# TinyDuino-noboard.net
KiCad netlist of a schematic drawn in EAGLE
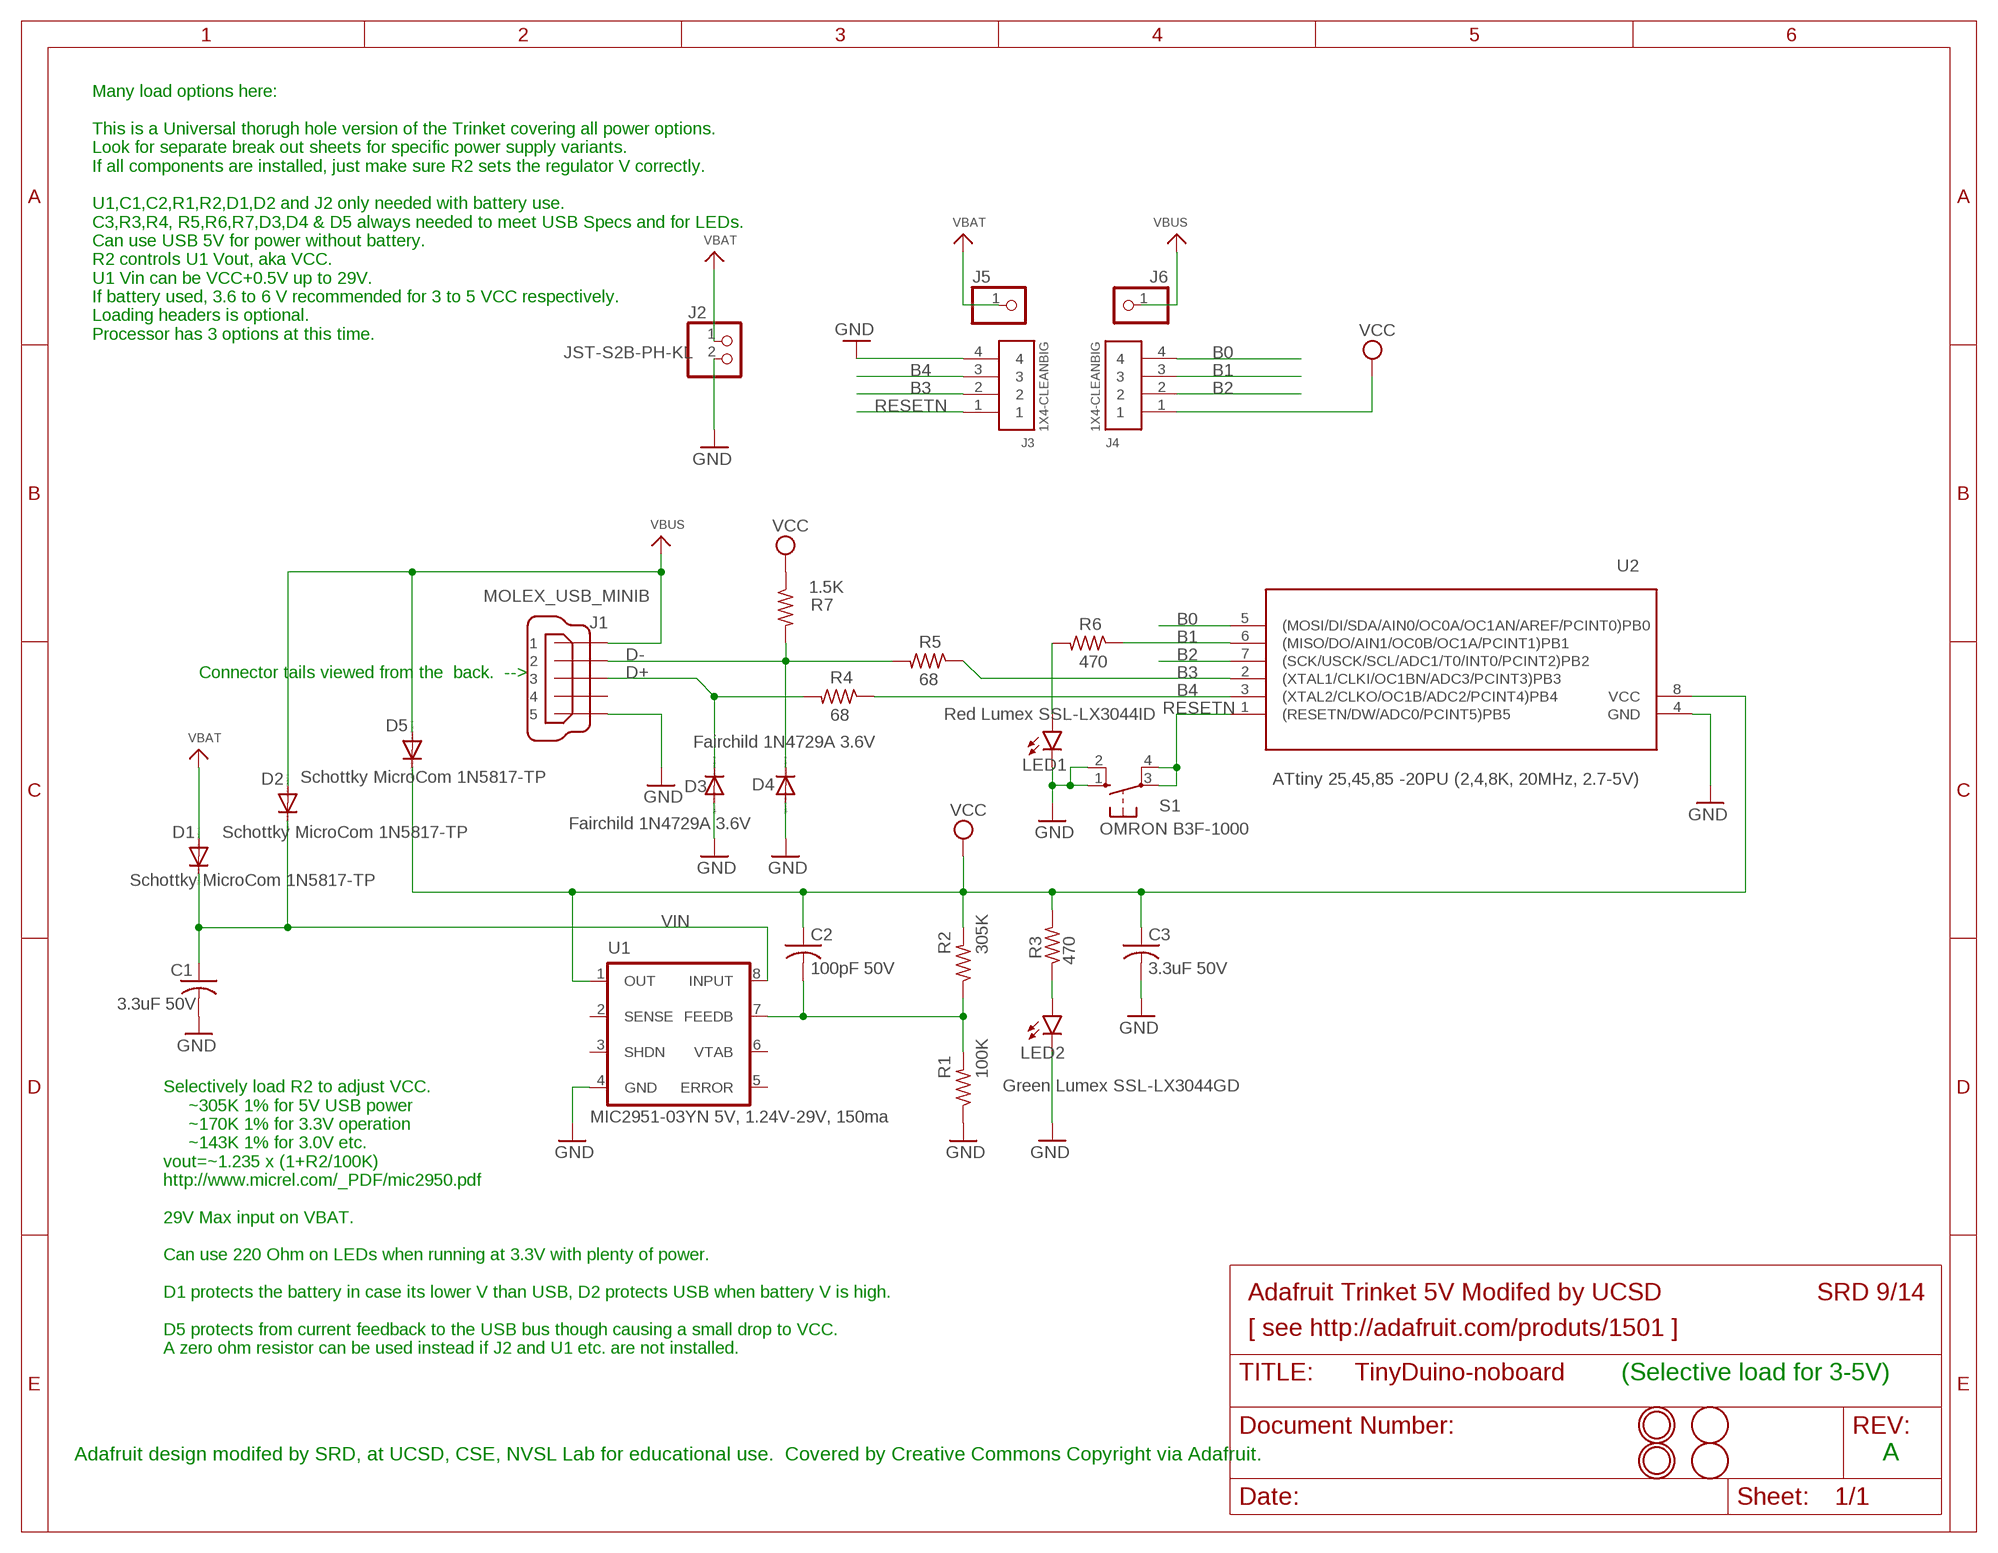
[diagram p0: schematic, sheet 1]

(export (version "E")
  (design (tool "Eeschema 10.0.6"))
  (components
    (comp (ref "C1")
      (value "3.3uF 50V")
      (footprint "eagle-import:C050-025X075")
      (fields (field (name "MFR") "TDK") (field (name "PARTNO") "FK20X7R1H335K"))
      (libsource (lib "eagle-import") (part "C-US050-025X075"))
    )
    (comp (ref "C2")
      (value "100pF 50V")
      (footprint "eagle-import:C050-025X075")
      (fields (field (name "MFR") "TDK") (field (name "PARTNO") "FK28C0G1H101J"))
      (libsource (lib "eagle-import") (part "C-US050-025X075"))
    )
    (comp (ref "C3")
      (value "3.3uF 50V")
      (footprint "eagle-import:C050-025X075")
      (fields (field (name "MFR") "TDK") (field (name "PARTNO") "FK20X7R1H335K"))
      (libsource (lib "eagle-import") (part "C-US050-025X075"))
    )
    (comp (ref "D1")
      (value "Schottky MicroCom 1N5817-TP")
      (footprint "eagle-import:DO41-7.6")
      (fields (field (name "MFR") "Micro Com.") (field (name "PARTNO") "1N5817-TP"))
      (libsource (lib "eagle-import") (part "DIODE-DO41-7.6"))
    )
    (comp (ref "D2")
      (value "Schottky MicroCom 1N5817-TP")
      (footprint "eagle-import:DO41-7.6")
      (fields (field (name "MFR") "Micro Com.") (field (name "PARTNO") "1N5817-TP"))
      (libsource (lib "eagle-import") (part "DIODE-DO41-7.6"))
    )
    (comp (ref "D3")
      (value "Fairchild 1N4729A 3.6V")
      (footprint "eagle-import:DO41-7.6")
      (fields (field (name "MFR") "Fairchild") (field (name "PARTNO") "1N4729A"))
      (libsource (lib "eagle-import") (part "DIODE-DO41-7.6"))
    )
    (comp (ref "D4")
      (value "Fairchild 1N4729A 3.6V")
      (footprint "eagle-import:DO41-7.6")
      (fields (field (name "MFR") "Fairchild") (field (name "PARTNO") "1N4729A"))
      (libsource (lib "eagle-import") (part "DIODE-DO41-7.6"))
    )
    (comp (ref "D5")
      (value "Schottky MicroCom 1N5817-TP")
      (footprint "eagle-import:DO41-7.6")
      (fields (field (name "MFR") "Micro Com.") (field (name "PARTNO") "1N5817-TP"))
      (libsource (lib "eagle-import") (part "DIODE-DO41-7.6"))
    )
    (comp (ref "J1")
      (value "MOLEX_USB_MINIB")
      (footprint "eagle-import:32005-601-ROUND")
      (fields (field (name "MFR") "Molex") (field (name "PARTNO") "0548190519"))
      (libsource (lib "eagle-import") (part "MOLEX_USB_MINIB"))
    )
    (comp (ref "J2")
      (value "JST-S2B-PH-KL")
      (footprint "eagle-import:JST_S2B_PH_KL")
      (fields (field (name "MFR") "JST") (field (name "PARTNO") "JST_S2B_PH_KL"))
      (libsource (lib "eagle-import") (part "CON_JST_PH_2PINJST_S2B_PH_KL"))
    )
    (comp (ref "J3")
      (value "1X4-CLEANBIG")
      (footprint "eagle-import:1X04-CLEANBIG")
      (libsource (lib "eagle-import") (part "1X4-CLEANBIG"))
    )
    (comp (ref "J4")
      (value "1X4-CLEANBIG")
      (footprint "eagle-import:1X04-CLEANBIG")
      (libsource (lib "eagle-import") (part "1X4-CLEANBIG"))
    )
    (comp (ref "J5")
      (value "PINHD-1X1CB")
      (footprint "eagle-import:1X01-CLEANBIG")
      (libsource (lib "eagle-import") (part "PINHD-1X1CB"))
    )
    (comp (ref "J6")
      (value "PINHD-1X1CB")
      (footprint "eagle-import:1X01-CLEANBIG")
      (libsource (lib "eagle-import") (part "PINHD-1X1CB"))
    )
    (comp (ref "LED1")
      (value "Red Lumex SSL-LX3044ID")
      (footprint "eagle-import:LED3MM")
      (fields (field (name "MFR") "Lumex") (field (name "PARTNO") "SSL-LX3044ID"))
      (libsource (lib "eagle-import") (part "LED3MM"))
    )
    (comp (ref "LED2")
      (value "Green Lumex SSL-LX3044GD")
      (footprint "eagle-import:LED3MM")
      (fields (field (name "MFR") "Lumex") (field (name "PARTNO") "SSL-LX3044GD"))
      (libsource (lib "eagle-import") (part "LED3MM"))
    )
    (comp (ref "R1")
      (value "100K")
      (footprint "eagle-import:0204_7")
      (fields (field (name "MFR") "Yageo") (field (name "PARTNO") "MFR-25FBF52-100K"))
      (libsource (lib "eagle-import") (part "R-US_0204/7"))
    )
    (comp (ref "R2")
      (value "305K")
      (footprint "eagle-import:0204_7")
      (fields (field (name "MFR") "Yageo") (field (name "PARTNO") "MFR-25FBF52-301K"))
      (libsource (lib "eagle-import") (part "R-US_0204/7"))
    )
    (comp (ref "R3")
      (value "470")
      (footprint "eagle-import:0204_7")
      (fields (field (name "MFR") "Yageo") (field (name "PARTNO") "CFR-12JB-52-470R"))
      (libsource (lib "eagle-import") (part "R-US_0204/7"))
    )
    (comp (ref "R4")
      (value "68")
      (footprint "eagle-import:0204_7")
      (fields (field (name "MFR") "Yageo") (field (name "PARTNO") "CFR-12JB-52-68R"))
      (libsource (lib "eagle-import") (part "R-US_0204/7"))
    )
    (comp (ref "R5")
      (value "68")
      (footprint "eagle-import:0204_7")
      (fields (field (name "MFR") "Yageo") (field (name "PARTNO") "CFR-12JB-52-68R"))
      (libsource (lib "eagle-import") (part "R-US_0204/7"))
    )
    (comp (ref "R6")
      (value "470")
      (footprint "eagle-import:0204_7")
      (fields (field (name "MFR") "Yageo") (field (name "PARTNO") "CFR-12JB-52-470R"))
      (libsource (lib "eagle-import") (part "R-US_0204/7"))
    )
    (comp (ref "R7")
      (value "1.5K")
      (footprint "eagle-import:0204_7")
      (fields (field (name "MFR") "Yageo") (field (name "PARTNO") "CFR-12JB-52-1K5"))
      (libsource (lib "eagle-import") (part "R-US_0204/7"))
    )
    (comp (ref "S1")
      (value "OMRON B3F-1000")
      (footprint "eagle-import:B3F-10XX")
      (fields (field (name "MPN") "B3F-1000") (field (name "MFR") "Omron"))
      (libsource (lib "eagle-import") (part "10-XX"))
    )
    (comp (ref "U1")
      (value "MIC2951-03YN 5V, 1.24V-29V, 150ma")
      (footprint "eagle-import:DIL08")
      (fields (field (name "MFR") "Micrel") (field (name "PARTNO") "MIC2951-03YN"))
      (libsource (lib "eagle-import") (part "MIC2951-03YNCN"))
    )
    (comp (ref "U2")
      (value "ATtiny 25,45,85 -20PU (2,4,8K, 20MHz, 2.7-5V)")
      (footprint "eagle-import:DIL08")
      (fields (field (name "MFR") "Atmel") (field (name "PARTNO") "ATTINY85-20PU-ND"))
      (libsource (lib "eagle-import") (part "ATTINY85P-20"))
    )
    (comp (ref "Z1")
      (value "MOUNTINGHOLE2.0")
      (footprint "eagle-import:MOUNTINGHOLE_2.0_PLATED")
      (libsource (lib "eagle-import") (part "MOUNTINGHOLE2.0"))
    )
    (comp (ref "Z2")
      (value "MOUNTINGHOLE2.0")
      (footprint "eagle-import:MOUNTINGHOLE_2.0_PLATED")
      (libsource (lib "eagle-import") (part "MOUNTINGHOLE2.0"))
    )
    (comp (ref "Z3")
      (value "FIDUCIAL")
      (footprint "eagle-import:FIDUCIAL_1MM")
      (libsource (lib "eagle-import") (part "FIDUCIAL"))
    )
    (comp (ref "Z4")
      (value "FIDUCIAL")
      (footprint "eagle-import:FIDUCIAL_1MM")
      (libsource (lib "eagle-import") (part "FIDUCIAL"))
    )
  )
  (nets
    (net (code "1") (name "/B0") (class "Default")
      (node (ref "J4") (pin "4") (pinfunction "4_4") (pintype "bidirectional"))
      (node (ref "U2") (pin "5") (pinfunction "(MOSI/DI/SDA/AIN0/OC0A/OC1AN/AREF/PCINT0)PB0_5") (pintype "bidirectional"))
    )
    (net (code "2") (name "/B1") (class "Default")
      (node (ref "J4") (pin "3") (pinfunction "3_3") (pintype "bidirectional"))
      (node (ref "R6") (pin "1") (pinfunction "1_1") (pintype "passive"))
      (node (ref "U2") (pin "6") (pinfunction "(MISO/DO/AIN1/OC0B/OC1A/PCINT1)PB1_6") (pintype "bidirectional"))
    )
    (net (code "3") (name "/B2") (class "Default")
      (node (ref "J4") (pin "2") (pinfunction "2_2") (pintype "bidirectional"))
      (node (ref "U2") (pin "7") (pinfunction "(SCK/USCK/SCL/ADC1/T0/INT0/PCINT2)PB2_7") (pintype "bidirectional"))
    )
    (net (code "4") (name "/B3") (class "Default")
      (node (ref "J3") (pin "2") (pinfunction "2_2") (pintype "bidirectional"))
      (node (ref "R5") (pin "1") (pinfunction "1_1") (pintype "passive"))
      (node (ref "U2") (pin "2") (pinfunction "(XTAL1/CLKI/OC1BN/ADC3/PCINT3)PB3_2") (pintype "bidirectional"))
    )
    (net (code "5") (name "/B4") (class "Default")
      (node (ref "J3") (pin "3") (pinfunction "3_3") (pintype "bidirectional"))
      (node (ref "R4") (pin "1") (pinfunction "1_1") (pintype "passive"))
      (node (ref "U2") (pin "3") (pinfunction "(XTAL2/CLKO/OC1B/ADC2/PCINT4)PB4_3") (pintype "bidirectional"))
    )
    (net (code "6") (name "/D+") (class "Default")
      (node (ref "D3") (pin "C") (pinfunction "C_C") (pintype "passive"))
      (node (ref "J1") (pin "3") (pinfunction "3_3") (pintype "passive"))
      (node (ref "R4") (pin "2") (pinfunction "2_2") (pintype "passive"))
    )
    (net (code "7") (name "/D-") (class "Default")
      (node (ref "D4") (pin "C") (pinfunction "C_C") (pintype "passive"))
      (node (ref "J1") (pin "2") (pinfunction "2_2") (pintype "passive"))
      (node (ref "R5") (pin "2") (pinfunction "2_2") (pintype "passive"))
      (node (ref "R7") (pin "2") (pinfunction "2_2") (pintype "passive"))
    )
    (net (code "8") (name "/RESETN") (class "Default")
      (node (ref "J3") (pin "1") (pinfunction "1_1") (pintype "bidirectional"))
      (node (ref "S1") (pin "3") (pinfunction "P_3") (pintype "passive"))
      (node (ref "S1") (pin "4") (pinfunction "P1_4") (pintype "passive"))
      (node (ref "U2") (pin "1") (pinfunction "(RESETN/DW/ADC0/PCINT5)PB5_1") (pintype "bidirectional"))
    )
    (net (code "9") (name "/VIN") (class "Default")
      (node (ref "C1") (pin "1") (pinfunction "1_1") (pintype "passive"))
      (node (ref "D1") (pin "C") (pinfunction "C_C") (pintype "passive"))
      (node (ref "D2") (pin "C") (pinfunction "C_C") (pintype "passive"))
      (node (ref "U1") (pin "8") (pinfunction "INPUT_8") (pintype "passive"))
    )
    (net (code "10") (name "GND") (class "Default")
      (node (ref "C1") (pin "2") (pinfunction "2_2") (pintype "passive"))
      (node (ref "C3") (pin "2") (pinfunction "2_2") (pintype "passive"))
      (node (ref "D3") (pin "A") (pinfunction "A_A") (pintype "passive"))
      (node (ref "D4") (pin "A") (pinfunction "A_A") (pintype "passive"))
      (node (ref "J1") (pin "5") (pinfunction "5_5") (pintype "passive"))
      (node (ref "J2") (pin "2") (pinfunction "2_2") (pintype "passive"))
      (node (ref "J3") (pin "4") (pinfunction "4_4") (pintype "bidirectional"))
      (node (ref "LED1") (pin "K") (pinfunction "C_K") (pintype "passive"))
      (node (ref "LED2") (pin "K") (pinfunction "C_K") (pintype "passive"))
      (node (ref "R1") (pin "1") (pinfunction "1_1") (pintype "passive"))
      (node (ref "S1") (pin "1") (pinfunction "S_1") (pintype "passive"))
      (node (ref "S1") (pin "2") (pinfunction "S1_2") (pintype "passive"))
      (node (ref "U1") (pin "4") (pinfunction "GND_4") (pintype "power_in"))
      (node (ref "U2") (pin "4") (pinfunction "GND_4") (pintype "bidirectional"))
    )
    (net (code "11") (name "Net-(LED1-PadA)") (class "Default")
      (node (ref "LED1") (pin "A") (pinfunction "A_A") (pintype "passive"))
      (node (ref "R6") (pin "2") (pinfunction "2_2") (pintype "passive"))
    )
    (net (code "12") (name "Net-(LED2-PadA)") (class "Default")
      (node (ref "LED2") (pin "A") (pinfunction "A_A") (pintype "passive"))
      (node (ref "R3") (pin "1") (pinfunction "1_1") (pintype "passive"))
    )
    (net (code "13") (name "Net-(U1-FEEDB)") (class "Default")
      (node (ref "C2") (pin "2") (pinfunction "2_2") (pintype "passive"))
      (node (ref "R1") (pin "2") (pinfunction "2_2") (pintype "passive"))
      (node (ref "R2") (pin "1") (pinfunction "1_1") (pintype "passive"))
      (node (ref "U1") (pin "7") (pinfunction "FEEDB_7") (pintype "output"))
    )
    (net (code "14") (name "VBAT") (class "Default")
      (node (ref "D1") (pin "A") (pinfunction "A_A") (pintype "passive"))
      (node (ref "J2") (pin "1") (pinfunction "1_1") (pintype "passive"))
      (node (ref "J5") (pin "1") (pinfunction "1_1") (pintype "passive"))
    )
    (net (code "15") (name "VBUS") (class "Default")
      (node (ref "D2") (pin "A") (pinfunction "A_A") (pintype "passive"))
      (node (ref "D5") (pin "A") (pinfunction "A_A") (pintype "passive"))
      (node (ref "J1") (pin "1") (pinfunction "1_1") (pintype "passive"))
      (node (ref "J6") (pin "1") (pinfunction "1_1") (pintype "passive"))
    )
    (net (code "16") (name "VCC") (class "Default")
      (node (ref "C2") (pin "1") (pinfunction "1_1") (pintype "passive"))
      (node (ref "C3") (pin "1") (pinfunction "1_1") (pintype "passive"))
      (node (ref "D5") (pin "C") (pinfunction "C_C") (pintype "passive"))
      (node (ref "J4") (pin "1") (pinfunction "1_1") (pintype "bidirectional"))
      (node (ref "R2") (pin "2") (pinfunction "2_2") (pintype "passive"))
      (node (ref "R3") (pin "2") (pinfunction "2_2") (pintype "passive"))
      (node (ref "R7") (pin "1") (pinfunction "1_1") (pintype "passive"))
      (node (ref "U1") (pin "1") (pinfunction "OUT_1") (pintype "output"))
      (node (ref "U2") (pin "8") (pinfunction "VCC_8") (pintype "bidirectional"))
    )
    (net (code "17") (name "unconnected-(J1-Pad4)") (class "Default")
      (node (ref "J1") (pin "4") (pinfunction "4_4") (pintype "passive"))
    )
    (net (code "18") (name "unconnected-(U1-ERROR-Pad5)") (class "Default")
      (node (ref "U1") (pin "5") (pinfunction "ERROR_5") (pintype "output"))
    )
    (net (code "19") (name "unconnected-(U1-SENSE-Pad2)") (class "Default")
      (node (ref "U1") (pin "2") (pinfunction "SENSE_2") (pintype "input"))
    )
    (net (code "20") (name "unconnected-(U1-SHDN-Pad3)") (class "Default")
      (node (ref "U1") (pin "3") (pinfunction "SHDN_3") (pintype "input"))
    )
    (net (code "21") (name "unconnected-(U1-VTAB-Pad6)") (class "Default")
      (node (ref "U1") (pin "6") (pinfunction "VTAB_6") (pintype "input"))
    )
  )
)
